# NUC.net
KiCad netlist of a schematic drawn in Altium Designer
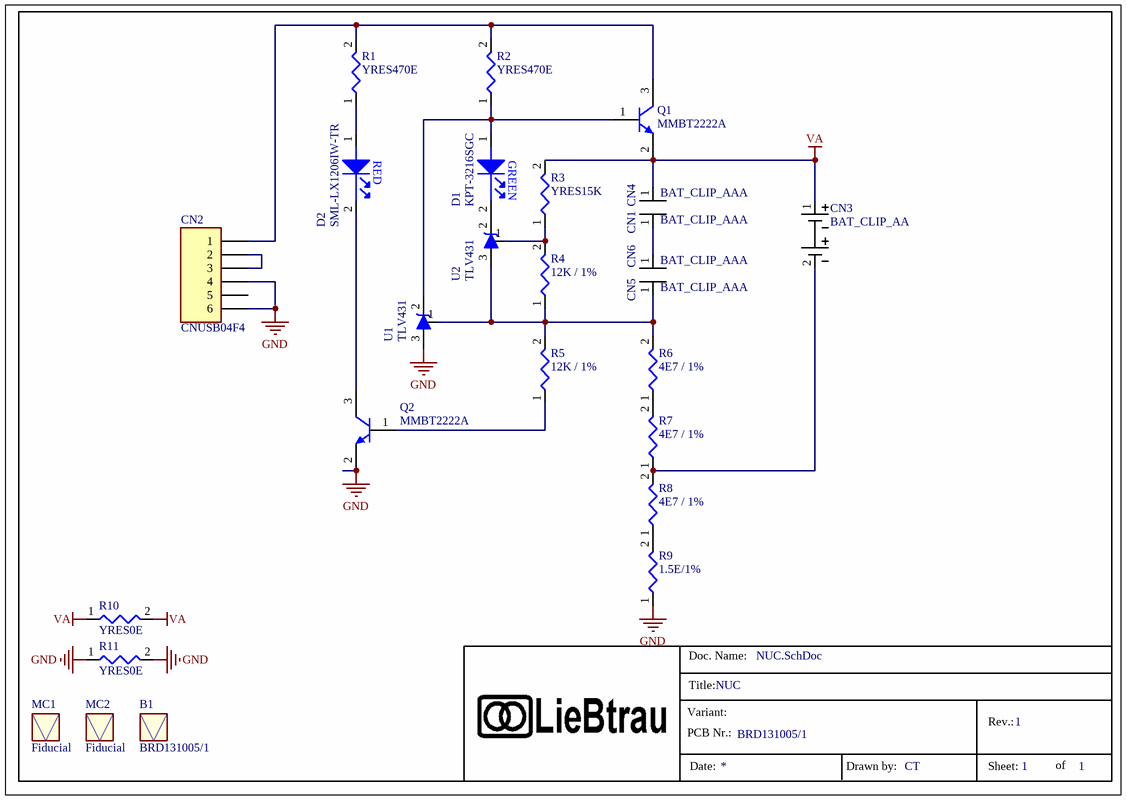
[diagram p0: NUC.SchDoc]

(export (version "E")
  (design (tool "Eeschema 10.0.6"))
  (components
    (comp (ref "B1")
      (value "~")
      (footprint "MC_BoardNr")
      (fields (field (name "PART NUMBER") "BARE_PCB"))
      (libsource (lib "Testing") (part "BD_PCB"))
    )
    (comp (ref "CN1")
      (value "BAT_CLIP_AAA")
      (footprint "CN_BAT_CLIP_AAA_Keystone_55")
      (fields (field (name "MANUFACTURER") "Keystone"))
      (libsource (lib "Testing") (part "CN_BAT_CLIP"))
    )
    (comp (ref "CN2")
      (value "CNUSB04F4")
      (footprint "CN_USB_AB_mini")
      (fields (field (name "MANUFACTURER") "Multicomp"))
      (libsource (lib "Testing") (part "CN_6P"))
    )
    (comp (ref "CN3")
      (value "BAT_CLIP_AA")
      (footprint "CN_BAT_CLIP_AA_KEYSTONE_2462")
      (fields (field (name "MANUFACTURER") "Keystone"))
      (libsource (lib "Testing") (part "CN_BAT_CLIP_2CELLS"))
    )
    (comp (ref "CN4")
      (value "BAT_CLIP_AAA")
      (footprint "CN_BAT_CLIP_AAA_Keystone_55")
      (fields (field (name "MANUFACTURER") "Keystone"))
      (libsource (lib "Testing") (part "CN_BAT_CLIP"))
    )
    (comp (ref "CN5")
      (value "BAT_CLIP_AAA")
      (footprint "CN_BAT_CLIP_AAA_Keystone_55")
      (fields (field (name "MANUFACTURER") "Keystone"))
      (libsource (lib "Testing") (part "CN_BAT_CLIP"))
    )
    (comp (ref "CN6")
      (value "BAT_CLIP_AAA")
      (footprint "CN_BAT_CLIP_AAA_Keystone_55")
      (fields (field (name "MANUFACTURER") "Keystone"))
      (libsource (lib "Testing") (part "CN_BAT_CLIP"))
    )
    (comp (ref "D1")
      (value "KPT-3216SGC")
      (footprint "DI_LED_1206_G")
      (fields (field (name "MANUFACTURER") "Kingbright"))
      (libsource (lib "Testing") (part "DI_LED_GREEN"))
    )
    (comp (ref "D2")
      (value "SML-LX1206IW-TR")
      (footprint "DI_LED_1206_R")
      (fields (field (name "MANUFACTURER") "LUMEX"))
      (libsource (lib "Testing") (part "DI_LED_RED"))
    )
    (comp (ref "MC1")
      (value "Fiducial")
      (footprint "MC_FIDUCIAL")
      (libsource (lib "Testing") (part "MC_MechPart_No_BOM"))
    )
    (comp (ref "MC2")
      (value "Fiducial")
      (footprint "MC_FIDUCIAL")
      (libsource (lib "Testing") (part "MC_MechPart_No_BOM"))
    )
    (comp (ref "Q1")
      (value "MMBT2222A")
      (footprint "SC_SOT23")
      (description "Amplifier Transistor NPN Silicon")
      (fields (field (name "MANUFACTURER") "Fairchild Semiconductor"))
      (libsource (lib "Testing") (part "TR_NPN_1"))
    )
    (comp (ref "Q2")
      (value "MMBT2222A")
      (footprint "SC_SOT23")
      (description "Amplifier Transistor NPN Silicon")
      (fields (field (name "MANUFACTURER") "Fairchild Semiconductor"))
      (libsource (lib "Testing") (part "TR_NPN_1"))
    )
    (comp (ref "R1")
      (value "YRES470E")
      (footprint "RE_1206")
      (description "Resistor")
      (fields (field (name "MANUFACTURER") "Multicomp"))
      (libsource (lib "Testing") (part "RE_RES"))
    )
    (comp (ref "R2")
      (value "YRES470E")
      (footprint "RE_1206")
      (description "Resistor")
      (fields (field (name "MANUFACTURER") "Multicomp"))
      (libsource (lib "Testing") (part "RE_RES"))
    )
    (comp (ref "R3")
      (value "YRES15K")
      (footprint "RE_1206")
      (description "Resistor")
      (fields (field (name "MANUFACTURER") "Welwyn"))
      (libsource (lib "Testing") (part "RE_RES"))
    )
    (comp (ref "R4")
      (value "12K / 1%")
      (footprint "RE_1206")
      (description "Resistor")
      (fields (field (name "PART NUMBER") "RC1206FR-0712KL") (field (name "MANUFACTURER") "YAGEO (PHYCOMP)"))
      (libsource (lib "Testing") (part "RE_RES"))
    )
    (comp (ref "R5")
      (value "12K / 1%")
      (footprint "RE_1206")
      (description "Resistor")
      (fields (field (name "PART NUMBER") "RC1206FR-0712KL") (field (name "MANUFACTURER") "YAGEO (PHYCOMP)"))
      (libsource (lib "Testing") (part "RE_RES"))
    )
    (comp (ref "R6")
      (value "4E7 / 1%")
      (footprint "RE_1206")
      (description "Resistor")
      (fields (field (name "PART NUMBER") "ASC1206-4R7FT5") (field (name "MANUFACTURER") "Welwyn"))
      (libsource (lib "Testing") (part "RE_RES"))
    )
    (comp (ref "R7")
      (value "4E7 / 1%")
      (footprint "RE_1206")
      (description "Resistor")
      (fields (field (name "PART NUMBER") "ASC1206-4R7FT5") (field (name "MANUFACTURER") "Welwyn"))
      (libsource (lib "Testing") (part "RE_RES"))
    )
    (comp (ref "R8")
      (value "4E7 / 1%")
      (footprint "RE_1206")
      (description "Resistor")
      (fields (field (name "PART NUMBER") "ASC1206-4R7FT5") (field (name "MANUFACTURER") "Welwyn"))
      (libsource (lib "Testing") (part "RE_RES"))
    )
    (comp (ref "R9")
      (value "1.5E/1%")
      (footprint "RE_1206")
      (description "Resistor")
      (fields (field (name "PART NUMBER") "MCSR12W1R50FTL") (field (name "MANUFACTURER") "Multicomp"))
      (libsource (lib "Testing") (part "RE_RES"))
    )
    (comp (ref "R10")
      (value "YRES0E")
      (footprint "RE_1206")
      (description "Resistor")
      (fields (field (name "MANUFACTURER") "Vishay Draloric"))
      (libsource (lib "Testing") (part "RE_RES"))
    )
    (comp (ref "R11")
      (value "YRES0E")
      (footprint "RE_1206")
      (description "Resistor")
      (fields (field (name "MANUFACTURER") "Vishay Draloric"))
      (libsource (lib "Testing") (part "RE_RES"))
    )
    (comp (ref "U1")
      (value "TLV431")
      (footprint "SC_SOT23")
      (fields (field (name "MANUFACTURER") "Diodes Zetex"))
      (libsource (lib "Testing") (part "IC_TLV431"))
    )
    (comp (ref "U2")
      (value "TLV431")
      (footprint "SC_SOT23")
      (fields (field (name "MANUFACTURER") "Diodes Zetex"))
      (libsource (lib "Testing") (part "IC_TLV431"))
    )
  )
  (nets
    (net (code "1") (name "GND") (class "Default")
      (node (ref "CN2") (pin "4") (pinfunction "4_4") (pintype "passive"))
      (node (ref "CN2") (pin "6") (pinfunction "6_6") (pintype "passive"))
      (node (ref "Q2") (pin "2") (pinfunction "B_2") (pintype "passive"))
      (node (ref "R11") (pin "1") (pinfunction "1_1") (pintype "passive"))
      (node (ref "R11") (pin "2") (pinfunction "2_2") (pintype "passive"))
      (node (ref "R9") (pin "1") (pinfunction "1_1") (pintype "passive"))
      (node (ref "U1") (pin "3") (pinfunction "A_3") (pintype "passive"))
    )
    (net (code "2") (name "Net-(CN1-Pad1)") (class "Default")
      (node (ref "CN1") (pin "1") (pintype "passive"))
      (node (ref "CN6") (pin "1") (pintype "passive"))
    )
    (net (code "3") (name "Net-(CN2-Pad2)") (class "Default")
      (node (ref "CN2") (pin "2") (pinfunction "2_2") (pintype "passive"))
      (node (ref "CN2") (pin "3") (pinfunction "3_3") (pintype "passive"))
    )
    (net (code "4") (name "Net-(CN3--)") (class "Default")
      (node (ref "CN3") (pin "2") (pinfunction "-_2") (pintype "passive"))
      (node (ref "R7") (pin "1") (pinfunction "1_1") (pintype "passive"))
      (node (ref "R8") (pin "2") (pinfunction "2_2") (pintype "passive"))
    )
    (net (code "5") (name "Net-(D1-A)") (class "Default")
      (node (ref "D1") (pin "1") (pinfunction "A_1") (pintype "passive"))
      (node (ref "Q1") (pin "1") (pinfunction "C_1") (pintype "passive"))
      (node (ref "R2") (pin "1") (pinfunction "1_1") (pintype "passive"))
      (node (ref "U1") (pin "2") (pinfunction "C_2") (pintype "passive"))
    )
    (net (code "6") (name "Net-(D1-C)") (class "Default")
      (node (ref "D1") (pin "2") (pinfunction "C_2") (pintype "passive"))
      (node (ref "U2") (pin "2") (pinfunction "C_2") (pintype "passive"))
    )
    (net (code "7") (name "Net-(D2-A)") (class "Default")
      (node (ref "D2") (pin "1") (pinfunction "A_1") (pintype "passive"))
      (node (ref "R1") (pin "1") (pinfunction "1_1") (pintype "passive"))
    )
    (net (code "8") (name "Net-(D2-C)") (class "Default")
      (node (ref "D2") (pin "2") (pinfunction "C_2") (pintype "passive"))
      (node (ref "Q2") (pin "3") (pinfunction "E_3") (pintype "passive"))
    )
    (net (code "9") (name "Net-(Q1-E)") (class "Default")
      (node (ref "CN2") (pin "1") (pinfunction "1_1") (pintype "passive"))
      (node (ref "Q1") (pin "3") (pinfunction "E_3") (pintype "passive"))
      (node (ref "R1") (pin "2") (pinfunction "2_2") (pintype "passive"))
      (node (ref "R2") (pin "2") (pinfunction "2_2") (pintype "passive"))
    )
    (net (code "10") (name "Net-(Q2-C)") (class "Default")
      (node (ref "Q2") (pin "1") (pinfunction "C_1") (pintype "passive"))
      (node (ref "R5") (pin "1") (pinfunction "1_1") (pintype "passive"))
    )
    (net (code "11") (name "Net-(R6-Pad1)") (class "Default")
      (node (ref "R6") (pin "1") (pinfunction "1_1") (pintype "passive"))
      (node (ref "R7") (pin "2") (pinfunction "2_2") (pintype "passive"))
    )
    (net (code "12") (name "Net-(R8-Pad1)") (class "Default")
      (node (ref "R8") (pin "1") (pinfunction "1_1") (pintype "passive"))
      (node (ref "R9") (pin "2") (pinfunction "2_2") (pintype "passive"))
    )
    (net (code "13") (name "Net-(U1-Ref)") (class "Default")
      (node (ref "CN5") (pin "1") (pintype "passive"))
      (node (ref "R4") (pin "1") (pinfunction "1_1") (pintype "passive"))
      (node (ref "R5") (pin "2") (pinfunction "2_2") (pintype "passive"))
      (node (ref "R6") (pin "2") (pinfunction "2_2") (pintype "passive"))
      (node (ref "U1") (pin "1") (pinfunction "Ref_1") (pintype "passive"))
      (node (ref "U2") (pin "3") (pinfunction "A_3") (pintype "passive"))
    )
    (net (code "14") (name "Net-(U2-Ref)") (class "Default")
      (node (ref "R3") (pin "1") (pinfunction "1_1") (pintype "passive"))
      (node (ref "R4") (pin "2") (pinfunction "2_2") (pintype "passive"))
      (node (ref "U2") (pin "1") (pinfunction "Ref_1") (pintype "passive"))
    )
    (net (code "15") (name "VA") (class "Default")
      (node (ref "CN3") (pin "1") (pinfunction "+_1") (pintype "passive"))
      (node (ref "CN4") (pin "1") (pintype "passive"))
      (node (ref "Q1") (pin "2") (pinfunction "B_2") (pintype "passive"))
      (node (ref "R10") (pin "1") (pinfunction "1_1") (pintype "passive"))
      (node (ref "R10") (pin "2") (pinfunction "2_2") (pintype "passive"))
      (node (ref "R3") (pin "2") (pinfunction "2_2") (pintype "passive"))
    )
    (net (code "16") (name "unconnected-(CN2-Pad5)") (class "Default")
      (node (ref "CN2") (pin "5") (pinfunction "5_5") (pintype "passive"))
    )
  )
)
